# teaspoon.net
KiCad netlist of a schematic drawn in EAGLE
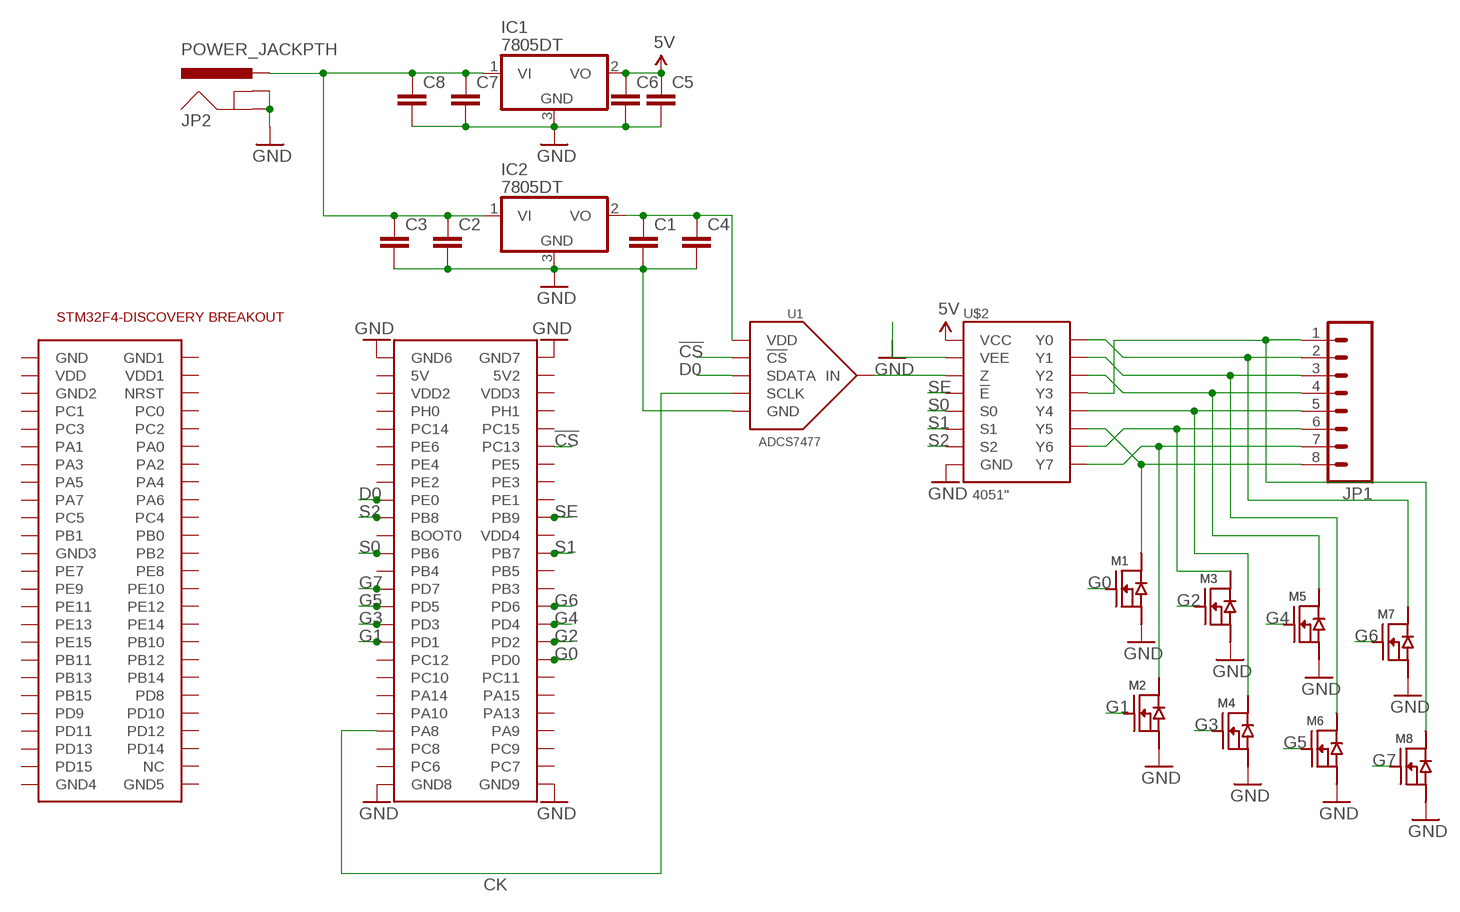
[diagram p0: schematic, sheet 1]

(export (version "E")
  (design (tool "Eeschema 10.0.6"))
  (components
    (comp (ref "C1")
      (value "C-EUC0805")
      (footprint "eagle-import:C0805")
      (libsource (lib "eagle-import") (part "C-EUC0805"))
    )
    (comp (ref "C2")
      (value "C-EUC0805")
      (footprint "eagle-import:C0805")
      (libsource (lib "eagle-import") (part "C-EUC0805"))
    )
    (comp (ref "C3")
      (value "C-EUC0805")
      (footprint "eagle-import:C0805")
      (libsource (lib "eagle-import") (part "C-EUC0805"))
    )
    (comp (ref "C4")
      (value "C-EUC0805")
      (footprint "eagle-import:C0805")
      (libsource (lib "eagle-import") (part "C-EUC0805"))
    )
    (comp (ref "C5")
      (value "C-EUC0805")
      (footprint "eagle-import:C0805")
      (libsource (lib "eagle-import") (part "C-EUC0805"))
    )
    (comp (ref "C6")
      (value "C-EUC0805")
      (footprint "eagle-import:C0805")
      (libsource (lib "eagle-import") (part "C-EUC0805"))
    )
    (comp (ref "C7")
      (value "C-EUC0805")
      (footprint "eagle-import:C0805")
      (libsource (lib "eagle-import") (part "C-EUC0805"))
    )
    (comp (ref "C8")
      (value "C-EUC0805")
      (footprint "eagle-import:C0805")
      (libsource (lib "eagle-import") (part "C-EUC0805"))
    )
    (comp (ref "IC1")
      (value "7805DT")
      (footprint "eagle-import:TO252")
      (libsource (lib "eagle-import") (part "78DT05"))
    )
    (comp (ref "IC2")
      (value "7805DT")
      (footprint "eagle-import:TO252")
      (libsource (lib "eagle-import") (part "78DT05"))
    )
    (comp (ref "JP1")
      (value "M08LONGPADS")
      (footprint "eagle-import:1X08_LONGPADS")
      (libsource (lib "eagle-import") (part "M08LONGPADS"))
    )
    (comp (ref "JP2")
      (value "POWER_JACKPTH")
      (footprint "eagle-import:POWER_JACK_PTH")
      (libsource (lib "eagle-import") (part "POWER_JACKPTH"))
    )
    (comp (ref "M1")
      (value "N-FET")
      (footprint "eagle-import:SOT23-3")
      (libsource (lib "eagle-import") (part "N-FET"))
    )
    (comp (ref "M2")
      (value "N-FET")
      (footprint "eagle-import:SOT23-3")
      (libsource (lib "eagle-import") (part "N-FET"))
    )
    (comp (ref "M3")
      (value "N-FET")
      (footprint "eagle-import:SOT23-3")
      (libsource (lib "eagle-import") (part "N-FET"))
    )
    (comp (ref "M4")
      (value "N-FET")
      (footprint "eagle-import:SOT23-3")
      (libsource (lib "eagle-import") (part "N-FET"))
    )
    (comp (ref "M5")
      (value "N-FET")
      (footprint "eagle-import:SOT23-3")
      (libsource (lib "eagle-import") (part "N-FET"))
    )
    (comp (ref "M6")
      (value "N-FET")
      (footprint "eagle-import:SOT23-3")
      (libsource (lib "eagle-import") (part "N-FET"))
    )
    (comp (ref "M7")
      (value "N-FET")
      (footprint "eagle-import:SOT23-3")
      (libsource (lib "eagle-import") (part "N-FET"))
    )
    (comp (ref "M8")
      (value "N-FET")
      (footprint "eagle-import:SOT23-3")
      (libsource (lib "eagle-import") (part "N-FET"))
    )
    (comp (ref "U$1")
      (value "STM32F4-DISCOVERY")
      (footprint "eagle-import:STM32F4-DISCOVERY")
      (libsource (lib "eagle-import") (part "STM32F4-DISCOVERY"))
    )
    (comp (ref "U$2")
      (value "4051\"")
      (footprint "eagle-import:TSSOP-16")
      (libsource (lib "eagle-import") (part "4051{dblquote}"))
    )
    (comp (ref "U1")
      (value "ADCS7477")
      (footprint "eagle-import:SOT-23-6")
      (libsource (lib "eagle-import") (part "ADCS7477"))
    )
  )
  (nets
    (net (code "1") (name "/CK") (class "Default")
      (node (ref "U$1") (pin "P$93") (pinfunction "PA8_P$93") (pintype "bidirectional"))
      (node (ref "U1") (pin "P$4") (pinfunction "SCLK_P$4") (pintype "bidirectional"))
    )
    (net (code "2") (name "/D0") (class "Default")
      (node (ref "U$1") (pin "P$67") (pinfunction "PE0_P$67") (pintype "bidirectional"))
      (node (ref "U1") (pin "P$5") (pinfunction "SDATA_P$5") (pintype "bidirectional"))
    )
    (net (code "3") (name "/G0") (class "Default")
      (node (ref "M1") (pin "1") (pinfunction "G_1") (pintype "bidirectional"))
      (node (ref "U$1") (pin "P$86") (pinfunction "PD0_P$86") (pintype "bidirectional"))
    )
    (net (code "4") (name "/G1") (class "Default")
      (node (ref "M2") (pin "1") (pinfunction "G_1") (pintype "bidirectional"))
      (node (ref "U$1") (pin "P$83") (pinfunction "PD1_P$83") (pintype "bidirectional"))
    )
    (net (code "5") (name "/G2") (class "Default")
      (node (ref "M3") (pin "1") (pinfunction "G_1") (pintype "bidirectional"))
      (node (ref "U$1") (pin "P$84") (pinfunction "PD2_P$84") (pintype "bidirectional"))
    )
    (net (code "6") (name "/G3") (class "Default")
      (node (ref "M4") (pin "1") (pinfunction "G_1") (pintype "bidirectional"))
      (node (ref "U$1") (pin "P$81") (pinfunction "PD3_P$81") (pintype "bidirectional"))
    )
    (net (code "7") (name "/G4") (class "Default")
      (node (ref "M5") (pin "1") (pinfunction "G_1") (pintype "bidirectional"))
      (node (ref "U$1") (pin "P$82") (pinfunction "PD4_P$82") (pintype "bidirectional"))
    )
    (net (code "8") (name "/G5") (class "Default")
      (node (ref "M6") (pin "1") (pinfunction "G_1") (pintype "bidirectional"))
      (node (ref "U$1") (pin "P$79") (pinfunction "PD5_P$79") (pintype "bidirectional"))
    )
    (net (code "9") (name "/G6") (class "Default")
      (node (ref "M7") (pin "1") (pinfunction "G_1") (pintype "bidirectional"))
      (node (ref "U$1") (pin "P$80") (pinfunction "PD6_P$80") (pintype "bidirectional"))
    )
    (net (code "10") (name "/G7") (class "Default")
      (node (ref "M8") (pin "1") (pinfunction "G_1") (pintype "bidirectional"))
      (node (ref "U$1") (pin "P$77") (pinfunction "PD7_P$77") (pintype "bidirectional"))
    )
    (net (code "11") (name "/S0") (class "Default")
      (node (ref "U$1") (pin "P$73") (pinfunction "PB6_P$73") (pintype "bidirectional"))
      (node (ref "U$2") (pin "P$11") (pinfunction "S0_P$11") (pintype "bidirectional"))
    )
    (net (code "12") (name "/S1") (class "Default")
      (node (ref "U$1") (pin "P$74") (pinfunction "PB7_P$74") (pintype "bidirectional"))
      (node (ref "U$2") (pin "P$10") (pinfunction "S1_P$10") (pintype "bidirectional"))
    )
    (net (code "13") (name "/S2") (class "Default")
      (node (ref "U$1") (pin "P$69") (pinfunction "PB8_P$69") (pintype "bidirectional"))
      (node (ref "U$2") (pin "P$9") (pinfunction "S2_P$9") (pintype "bidirectional"))
    )
    (net (code "14") (name "/SE") (class "Default")
      (node (ref "U$1") (pin "P$70") (pinfunction "PB9_P$70") (pintype "bidirectional"))
      (node (ref "U$2") (pin "P$6") (pinfunction "~{E}_P$6") (pintype "bidirectional"))
    )
    (net (code "15") (name "/~{CS}") (class "Default")
      (node (ref "U$1") (pin "P$62") (pinfunction "PC13_P$62") (pintype "bidirectional"))
      (node (ref "U1") (pin "P$6") (pinfunction "~{CS}_P$6") (pintype "bidirectional"))
    )
    (net (code "16") (name "5V") (class "Default")
      (node (ref "C5") (pin "1") (pinfunction "1_1") (pintype "passive"))
      (node (ref "C6") (pin "1") (pinfunction "1_1") (pintype "passive"))
      (node (ref "IC1") (pin "2") (pinfunction "VO_2") (pintype "passive"))
      (node (ref "U$2") (pin "P$16") (pinfunction "VCC_P$16") (pintype "bidirectional"))
    )
    (net (code "17") (name "GND") (class "Default")
      (node (ref "C1") (pin "2") (pinfunction "2_2") (pintype "passive"))
      (node (ref "C2") (pin "2") (pinfunction "2_2") (pintype "passive"))
      (node (ref "C3") (pin "2") (pinfunction "2_2") (pintype "passive"))
      (node (ref "C4") (pin "2") (pinfunction "2_2") (pintype "passive"))
      (node (ref "C5") (pin "2") (pinfunction "2_2") (pintype "passive"))
      (node (ref "C6") (pin "2") (pinfunction "2_2") (pintype "passive"))
      (node (ref "C7") (pin "2") (pinfunction "2_2") (pintype "passive"))
      (node (ref "C8") (pin "2") (pinfunction "2_2") (pintype "passive"))
      (node (ref "IC1") (pin "3") (pinfunction "GND_3") (pintype "passive"))
      (node (ref "IC2") (pin "3") (pinfunction "GND_3") (pintype "passive"))
      (node (ref "JP2") (pin "GND") (pinfunction "GND_GND") (pintype "bidirectional"))
      (node (ref "JP2") (pin "GNDBREAK") (pinfunction "GNDBREAK_GNDBREAK") (pintype "bidirectional"))
      (node (ref "M1") (pin "2") (pinfunction "S_2") (pintype "bidirectional"))
      (node (ref "M2") (pin "2") (pinfunction "S_2") (pintype "bidirectional"))
      (node (ref "M3") (pin "2") (pinfunction "S_2") (pintype "bidirectional"))
      (node (ref "M4") (pin "2") (pinfunction "S_2") (pintype "bidirectional"))
      (node (ref "M5") (pin "2") (pinfunction "S_2") (pintype "bidirectional"))
      (node (ref "M6") (pin "2") (pinfunction "S_2") (pintype "bidirectional"))
      (node (ref "M7") (pin "2") (pinfunction "S_2") (pintype "bidirectional"))
      (node (ref "M8") (pin "2") (pinfunction "S_2") (pintype "bidirectional"))
      (node (ref "U$1") (pin "P$100") (pinfunction "GND9_P$100") (pintype "bidirectional"))
      (node (ref "U$1") (pin "P$51") (pinfunction "GND6_P$51") (pintype "bidirectional"))
      (node (ref "U$1") (pin "P$52") (pinfunction "GND7_P$52") (pintype "bidirectional"))
      (node (ref "U$1") (pin "P$99") (pinfunction "GND8_P$99") (pintype "bidirectional"))
      (node (ref "U$2") (pin "P$7") (pinfunction "VEE_P$7") (pintype "bidirectional"))
      (node (ref "U$2") (pin "P$8") (pinfunction "GND_P$8") (pintype "bidirectional"))
      (node (ref "U1") (pin "P$2") (pinfunction "GND_P$2") (pintype "bidirectional"))
    )
    (net (code "18") (name "Net-(IC1-VI)") (class "Default")
      (node (ref "C2") (pin "1") (pinfunction "1_1") (pintype "passive"))
      (node (ref "C3") (pin "1") (pinfunction "1_1") (pintype "passive"))
      (node (ref "C7") (pin "1") (pinfunction "1_1") (pintype "passive"))
      (node (ref "C8") (pin "1") (pinfunction "1_1") (pintype "passive"))
      (node (ref "IC1") (pin "1") (pinfunction "VI_1") (pintype "input"))
      (node (ref "IC2") (pin "1") (pinfunction "VI_1") (pintype "input"))
      (node (ref "JP2") (pin "PWR") (pinfunction "PWR_PWR") (pintype "bidirectional"))
    )
    (net (code "19") (name "Net-(IC2-VO)") (class "Default")
      (node (ref "C1") (pin "1") (pinfunction "1_1") (pintype "passive"))
      (node (ref "C4") (pin "1") (pinfunction "1_1") (pintype "passive"))
      (node (ref "IC2") (pin "2") (pinfunction "VO_2") (pintype "passive"))
      (node (ref "U1") (pin "P$1") (pinfunction "VDD_P$1") (pintype "bidirectional"))
    )
    (net (code "20") (name "Net-(M1-D)") (class "Default")
      (node (ref "JP1") (pin "8") (pinfunction "8_8") (pintype "passive"))
      (node (ref "M1") (pin "3") (pinfunction "D_3") (pintype "bidirectional"))
      (node (ref "U$2") (pin "P$5") (pinfunction "Y5_P$5") (pintype "bidirectional"))
    )
    (net (code "21") (name "Net-(M2-D)") (class "Default")
      (node (ref "JP1") (pin "7") (pinfunction "7_7") (pintype "passive"))
      (node (ref "M2") (pin "3") (pinfunction "D_3") (pintype "bidirectional"))
      (node (ref "U$2") (pin "P$4") (pinfunction "Y7_P$4") (pintype "bidirectional"))
    )
    (net (code "22") (name "Net-(M3-D)") (class "Default")
      (node (ref "JP1") (pin "6") (pinfunction "6_6") (pintype "passive"))
      (node (ref "M3") (pin "3") (pinfunction "D_3") (pintype "bidirectional"))
      (node (ref "U$2") (pin "P$2") (pinfunction "Y6_P$2") (pintype "bidirectional"))
    )
    (net (code "23") (name "Net-(M4-D)") (class "Default")
      (node (ref "JP1") (pin "5") (pinfunction "5_5") (pintype "passive"))
      (node (ref "M4") (pin "3") (pinfunction "D_3") (pintype "bidirectional"))
      (node (ref "U$2") (pin "P$1") (pinfunction "Y4_P$1") (pintype "bidirectional"))
    )
    (net (code "24") (name "Net-(M5-D)") (class "Default")
      (node (ref "JP1") (pin "4") (pinfunction "4_4") (pintype "passive"))
      (node (ref "M5") (pin "3") (pinfunction "D_3") (pintype "bidirectional"))
      (node (ref "U$2") (pin "P$15") (pinfunction "Y2_P$15") (pintype "bidirectional"))
    )
    (net (code "25") (name "Net-(M6-D)") (class "Default")
      (node (ref "JP1") (pin "3") (pinfunction "3_3") (pintype "passive"))
      (node (ref "M6") (pin "3") (pinfunction "D_3") (pintype "bidirectional"))
      (node (ref "U$2") (pin "P$14") (pinfunction "Y1_P$14") (pintype "bidirectional"))
    )
    (net (code "26") (name "Net-(M7-D)") (class "Default")
      (node (ref "JP1") (pin "2") (pinfunction "2_2") (pintype "passive"))
      (node (ref "M7") (pin "3") (pinfunction "D_3") (pintype "bidirectional"))
      (node (ref "U$2") (pin "P$13") (pinfunction "Y0_P$13") (pintype "bidirectional"))
    )
    (net (code "27") (name "Net-(M8-D)") (class "Default")
      (node (ref "JP1") (pin "1") (pinfunction "1_1") (pintype "passive"))
      (node (ref "M8") (pin "3") (pinfunction "D_3") (pintype "bidirectional"))
      (node (ref "U$2") (pin "P$12") (pinfunction "Y3_P$12") (pintype "bidirectional"))
    )
    (net (code "28") (name "Net-(U$2-Z)") (class "Default")
      (node (ref "U$2") (pin "P$3") (pinfunction "Z_P$3") (pintype "bidirectional"))
      (node (ref "U1") (pin "P$3") (pinfunction "IN_P$3") (pintype "bidirectional"))
    )
    (net (code "29") (name "unconnected-(U$1-5V-PadP$53)") (class "Default")
      (node (ref "U$1") (pin "P$53") (pinfunction "5V_P$53") (pintype "bidirectional"))
    )
    (net (code "30") (name "unconnected-(U$1-5V2-PadP$54)") (class "Default")
      (node (ref "U$1") (pin "P$54") (pinfunction "5V2_P$54") (pintype "bidirectional"))
    )
    (net (code "31") (name "unconnected-(U$1-BOOT0-PadP$71)") (class "Default")
      (node (ref "U$1") (pin "P$71") (pinfunction "BOOT0_P$71") (pintype "bidirectional"))
    )
    (net (code "32") (name "unconnected-(U$1-GND-PadP$1)") (class "Default")
      (node (ref "U$1") (pin "P$1") (pinfunction "GND_P$1") (pintype "bidirectional"))
    )
    (net (code "33") (name "unconnected-(U$1-GND1-PadP$2)") (class "Default")
      (node (ref "U$1") (pin "P$2") (pinfunction "GND1_P$2") (pintype "bidirectional"))
    )
    (net (code "34") (name "unconnected-(U$1-GND2-PadP$5)") (class "Default")
      (node (ref "U$1") (pin "P$5") (pinfunction "GND2_P$5") (pintype "bidirectional"))
    )
    (net (code "35") (name "unconnected-(U$1-GND3-PadP$23)") (class "Default")
      (node (ref "U$1") (pin "P$23") (pinfunction "GND3_P$23") (pintype "bidirectional"))
    )
    (net (code "36") (name "unconnected-(U$1-GND4-PadP$49)") (class "Default")
      (node (ref "U$1") (pin "P$49") (pinfunction "GND4_P$49") (pintype "bidirectional"))
    )
    (net (code "37") (name "unconnected-(U$1-GND5-PadP$50)") (class "Default")
      (node (ref "U$1") (pin "P$50") (pinfunction "GND5_P$50") (pintype "bidirectional"))
    )
    (net (code "38") (name "unconnected-(U$1-NC-PadP$48)") (class "Default")
      (node (ref "U$1") (pin "P$48") (pinfunction "NC_P$48") (pintype "bidirectional"))
    )
    (net (code "39") (name "unconnected-(U$1-NRST-PadP$6)") (class "Default")
      (node (ref "U$1") (pin "P$6") (pinfunction "NRST_P$6") (pintype "bidirectional"))
    )
    (net (code "40") (name "unconnected-(U$1-PA0-PadP$12)") (class "Default")
      (node (ref "U$1") (pin "P$12") (pinfunction "PA0_P$12") (pintype "bidirectional"))
    )
    (net (code "41") (name "unconnected-(U$1-PA1-PadP$11)") (class "Default")
      (node (ref "U$1") (pin "P$11") (pinfunction "PA1_P$11") (pintype "bidirectional"))
    )
    (net (code "42") (name "unconnected-(U$1-PA2-PadP$14)") (class "Default")
      (node (ref "U$1") (pin "P$14") (pinfunction "PA2_P$14") (pintype "bidirectional"))
    )
    (net (code "43") (name "unconnected-(U$1-PA3-PadP$13)") (class "Default")
      (node (ref "U$1") (pin "P$13") (pinfunction "PA3_P$13") (pintype "bidirectional"))
    )
    (net (code "44") (name "unconnected-(U$1-PA4-PadP$16)") (class "Default")
      (node (ref "U$1") (pin "P$16") (pinfunction "PA4_P$16") (pintype "bidirectional"))
    )
    (net (code "45") (name "unconnected-(U$1-PA5-PadP$15)") (class "Default")
      (node (ref "U$1") (pin "P$15") (pinfunction "PA5_P$15") (pintype "bidirectional"))
    )
    (net (code "46") (name "unconnected-(U$1-PA6-PadP$18)") (class "Default")
      (node (ref "U$1") (pin "P$18") (pinfunction "PA6_P$18") (pintype "bidirectional"))
    )
    (net (code "47") (name "unconnected-(U$1-PA7-PadP$17)") (class "Default")
      (node (ref "U$1") (pin "P$17") (pinfunction "PA7_P$17") (pintype "bidirectional"))
    )
    (net (code "48") (name "unconnected-(U$1-PA9-PadP$94)") (class "Default")
      (node (ref "U$1") (pin "P$94") (pinfunction "PA9_P$94") (pintype "bidirectional"))
    )
    (net (code "49") (name "unconnected-(U$1-PA10-PadP$91)") (class "Default")
      (node (ref "U$1") (pin "P$91") (pinfunction "PA10_P$91") (pintype "bidirectional"))
    )
    (net (code "50") (name "unconnected-(U$1-PA13-PadP$92)") (class "Default")
      (node (ref "U$1") (pin "P$92") (pinfunction "PA13_P$92") (pintype "bidirectional"))
    )
    (net (code "51") (name "unconnected-(U$1-PA14-PadP$89)") (class "Default")
      (node (ref "U$1") (pin "P$89") (pinfunction "PA14_P$89") (pintype "bidirectional"))
    )
    (net (code "52") (name "unconnected-(U$1-PA15-PadP$90)") (class "Default")
      (node (ref "U$1") (pin "P$90") (pinfunction "PA15_P$90") (pintype "bidirectional"))
    )
    (net (code "53") (name "unconnected-(U$1-PB0-PadP$22)") (class "Default")
      (node (ref "U$1") (pin "P$22") (pinfunction "PB0_P$22") (pintype "bidirectional"))
    )
    (net (code "54") (name "unconnected-(U$1-PB1-PadP$21)") (class "Default")
      (node (ref "U$1") (pin "P$21") (pinfunction "PB1_P$21") (pintype "bidirectional"))
    )
    (net (code "55") (name "unconnected-(U$1-PB2-PadP$24)") (class "Default")
      (node (ref "U$1") (pin "P$24") (pinfunction "PB2_P$24") (pintype "bidirectional"))
    )
    (net (code "56") (name "unconnected-(U$1-PB3-PadP$78)") (class "Default")
      (node (ref "U$1") (pin "P$78") (pinfunction "PB3_P$78") (pintype "bidirectional"))
    )
    (net (code "57") (name "unconnected-(U$1-PB4-PadP$75)") (class "Default")
      (node (ref "U$1") (pin "P$75") (pinfunction "PB4_P$75") (pintype "bidirectional"))
    )
    (net (code "58") (name "unconnected-(U$1-PB5-PadP$76)") (class "Default")
      (node (ref "U$1") (pin "P$76") (pinfunction "PB5_P$76") (pintype "bidirectional"))
    )
    (net (code "59") (name "unconnected-(U$1-PB10-PadP$34)") (class "Default")
      (node (ref "U$1") (pin "P$34") (pinfunction "PB10_P$34") (pintype "bidirectional"))
    )
    (net (code "60") (name "unconnected-(U$1-PB11-PadP$35)") (class "Default")
      (node (ref "U$1") (pin "P$35") (pinfunction "PB11_P$35") (pintype "bidirectional"))
    )
    (net (code "61") (name "unconnected-(U$1-PB12-PadP$36)") (class "Default")
      (node (ref "U$1") (pin "P$36") (pinfunction "PB12_P$36") (pintype "bidirectional"))
    )
    (net (code "62") (name "unconnected-(U$1-PB13-PadP$37)") (class "Default")
      (node (ref "U$1") (pin "P$37") (pinfunction "PB13_P$37") (pintype "bidirectional"))
    )
    (net (code "63") (name "unconnected-(U$1-PB14-PadP$38)") (class "Default")
      (node (ref "U$1") (pin "P$38") (pinfunction "PB14_P$38") (pintype "bidirectional"))
    )
    (net (code "64") (name "unconnected-(U$1-PB15-PadP$39)") (class "Default")
      (node (ref "U$1") (pin "P$39") (pinfunction "PB15_P$39") (pintype "bidirectional"))
    )
    (net (code "65") (name "unconnected-(U$1-PC0-PadP$8)") (class "Default")
      (node (ref "U$1") (pin "P$8") (pinfunction "PC0_P$8") (pintype "bidirectional"))
    )
    (net (code "66") (name "unconnected-(U$1-PC1-PadP$7)") (class "Default")
      (node (ref "U$1") (pin "P$7") (pinfunction "PC1_P$7") (pintype "bidirectional"))
    )
    (net (code "67") (name "unconnected-(U$1-PC2-PadP$10)") (class "Default")
      (node (ref "U$1") (pin "P$10") (pinfunction "PC2_P$10") (pintype "bidirectional"))
    )
    (net (code "68") (name "unconnected-(U$1-PC3-PadP$9)") (class "Default")
      (node (ref "U$1") (pin "P$9") (pinfunction "PC3_P$9") (pintype "bidirectional"))
    )
    (net (code "69") (name "unconnected-(U$1-PC4-PadP$20)") (class "Default")
      (node (ref "U$1") (pin "P$20") (pinfunction "PC4_P$20") (pintype "bidirectional"))
    )
    (net (code "70") (name "unconnected-(U$1-PC5-PadP$19)") (class "Default")
      (node (ref "U$1") (pin "P$19") (pinfunction "PC5_P$19") (pintype "bidirectional"))
    )
    (net (code "71") (name "unconnected-(U$1-PC6-PadP$97)") (class "Default")
      (node (ref "U$1") (pin "P$97") (pinfunction "PC6_P$97") (pintype "bidirectional"))
    )
    (net (code "72") (name "unconnected-(U$1-PC7-PadP$98)") (class "Default")
      (node (ref "U$1") (pin "P$98") (pinfunction "PC7_P$98") (pintype "bidirectional"))
    )
    (net (code "73") (name "unconnected-(U$1-PC8-PadP$95)") (class "Default")
      (node (ref "U$1") (pin "P$95") (pinfunction "PC8_P$95") (pintype "bidirectional"))
    )
    (net (code "74") (name "unconnected-(U$1-PC9-PadP$96)") (class "Default")
      (node (ref "U$1") (pin "P$96") (pinfunction "PC9_P$96") (pintype "bidirectional"))
    )
    (net (code "75") (name "unconnected-(U$1-PC10-PadP$87)") (class "Default")
      (node (ref "U$1") (pin "P$87") (pinfunction "PC10_P$87") (pintype "bidirectional"))
    )
    (net (code "76") (name "unconnected-(U$1-PC11-PadP$88)") (class "Default")
      (node (ref "U$1") (pin "P$88") (pinfunction "PC11_P$88") (pintype "bidirectional"))
    )
    (net (code "77") (name "unconnected-(U$1-PC12-PadP$85)") (class "Default")
      (node (ref "U$1") (pin "P$85") (pinfunction "PC12_P$85") (pintype "bidirectional"))
    )
    (net (code "78") (name "unconnected-(U$1-PC14-PadP$59)") (class "Default")
      (node (ref "U$1") (pin "P$59") (pinfunction "PC14_P$59") (pintype "bidirectional"))
    )
    (net (code "79") (name "unconnected-(U$1-PC15-PadP$60)") (class "Default")
      (node (ref "U$1") (pin "P$60") (pinfunction "PC15_P$60") (pintype "bidirectional"))
    )
    (net (code "80") (name "unconnected-(U$1-PD8-PadP$40)") (class "Default")
      (node (ref "U$1") (pin "P$40") (pinfunction "PD8_P$40") (pintype "bidirectional"))
    )
    (net (code "81") (name "unconnected-(U$1-PD9-PadP$41)") (class "Default")
      (node (ref "U$1") (pin "P$41") (pinfunction "PD9_P$41") (pintype "bidirectional"))
    )
    (net (code "82") (name "unconnected-(U$1-PD10-PadP$42)") (class "Default")
      (node (ref "U$1") (pin "P$42") (pinfunction "PD10_P$42") (pintype "bidirectional"))
    )
    (net (code "83") (name "unconnected-(U$1-PD11-PadP$43)") (class "Default")
      (node (ref "U$1") (pin "P$43") (pinfunction "PD11_P$43") (pintype "bidirectional"))
    )
    (net (code "84") (name "unconnected-(U$1-PD12-PadP$44)") (class "Default")
      (node (ref "U$1") (pin "P$44") (pinfunction "PD12_P$44") (pintype "bidirectional"))
    )
    (net (code "85") (name "unconnected-(U$1-PD13-PadP$45)") (class "Default")
      (node (ref "U$1") (pin "P$45") (pinfunction "PD13_P$45") (pintype "bidirectional"))
    )
    (net (code "86") (name "unconnected-(U$1-PD14-PadP$46)") (class "Default")
      (node (ref "U$1") (pin "P$46") (pinfunction "PD14_P$46") (pintype "bidirectional"))
    )
    (net (code "87") (name "unconnected-(U$1-PD15-PadP$47)") (class "Default")
      (node (ref "U$1") (pin "P$47") (pinfunction "PD15_P$47") (pintype "bidirectional"))
    )
    (net (code "88") (name "unconnected-(U$1-PE1-PadP$68)") (class "Default")
      (node (ref "U$1") (pin "P$68") (pinfunction "PE1_P$68") (pintype "bidirectional"))
    )
    (net (code "89") (name "unconnected-(U$1-PE2-PadP$65)") (class "Default")
      (node (ref "U$1") (pin "P$65") (pinfunction "PE2_P$65") (pintype "bidirectional"))
    )
    (net (code "90") (name "unconnected-(U$1-PE3-PadP$66)") (class "Default")
      (node (ref "U$1") (pin "P$66") (pinfunction "PE3_P$66") (pintype "bidirectional"))
    )
    (net (code "91") (name "unconnected-(U$1-PE4-PadP$63)") (class "Default")
      (node (ref "U$1") (pin "P$63") (pinfunction "PE4_P$63") (pintype "bidirectional"))
    )
    (net (code "92") (name "unconnected-(U$1-PE5-PadP$64)") (class "Default")
      (node (ref "U$1") (pin "P$64") (pinfunction "PE5_P$64") (pintype "bidirectional"))
    )
    (net (code "93") (name "unconnected-(U$1-PE6-PadP$61)") (class "Default")
      (node (ref "U$1") (pin "P$61") (pinfunction "PE6_P$61") (pintype "bidirectional"))
    )
    (net (code "94") (name "unconnected-(U$1-PE7-PadP$25)") (class "Default")
      (node (ref "U$1") (pin "P$25") (pinfunction "PE7_P$25") (pintype "bidirectional"))
    )
    (net (code "95") (name "unconnected-(U$1-PE8-PadP$26)") (class "Default")
      (node (ref "U$1") (pin "P$26") (pinfunction "PE8_P$26") (pintype "bidirectional"))
    )
    (net (code "96") (name "unconnected-(U$1-PE9-PadP$27)") (class "Default")
      (node (ref "U$1") (pin "P$27") (pinfunction "PE9_P$27") (pintype "bidirectional"))
    )
    (net (code "97") (name "unconnected-(U$1-PE10-PadP$28)") (class "Default")
      (node (ref "U$1") (pin "P$28") (pinfunction "PE10_P$28") (pintype "bidirectional"))
    )
    (net (code "98") (name "unconnected-(U$1-PE11-PadP$29)") (class "Default")
      (node (ref "U$1") (pin "P$29") (pinfunction "PE11_P$29") (pintype "bidirectional"))
    )
    (net (code "99") (name "unconnected-(U$1-PE12-PadP$30)") (class "Default")
      (node (ref "U$1") (pin "P$30") (pinfunction "PE12_P$30") (pintype "bidirectional"))
    )
    (net (code "100") (name "unconnected-(U$1-PE13-PadP$31)") (class "Default")
      (node (ref "U$1") (pin "P$31") (pinfunction "PE13_P$31") (pintype "bidirectional"))
    )
    (net (code "101") (name "unconnected-(U$1-PE14-PadP$32)") (class "Default")
      (node (ref "U$1") (pin "P$32") (pinfunction "PE14_P$32") (pintype "bidirectional"))
    )
    (net (code "102") (name "unconnected-(U$1-PE15-PadP$33)") (class "Default")
      (node (ref "U$1") (pin "P$33") (pinfunction "PE15_P$33") (pintype "bidirectional"))
    )
    (net (code "103") (name "unconnected-(U$1-PH0-PadP$57)") (class "Default")
      (node (ref "U$1") (pin "P$57") (pinfunction "PH0_P$57") (pintype "bidirectional"))
    )
    (net (code "104") (name "unconnected-(U$1-PH1-PadP$58)") (class "Default")
      (node (ref "U$1") (pin "P$58") (pinfunction "PH1_P$58") (pintype "bidirectional"))
    )
    (net (code "105") (name "unconnected-(U$1-VDD-PadP$3)") (class "Default")
      (node (ref "U$1") (pin "P$3") (pinfunction "VDD_P$3") (pintype "bidirectional"))
    )
    (net (code "106") (name "unconnected-(U$1-VDD1-PadP$4)") (class "Default")
      (node (ref "U$1") (pin "P$4") (pinfunction "VDD1_P$4") (pintype "bidirectional"))
    )
    (net (code "107") (name "unconnected-(U$1-VDD2-PadP$55)") (class "Default")
      (node (ref "U$1") (pin "P$55") (pinfunction "VDD2_P$55") (pintype "bidirectional"))
    )
    (net (code "108") (name "unconnected-(U$1-VDD3-PadP$56)") (class "Default")
      (node (ref "U$1") (pin "P$56") (pinfunction "VDD3_P$56") (pintype "bidirectional"))
    )
    (net (code "109") (name "unconnected-(U$1-VDD4-PadP$72)") (class "Default")
      (node (ref "U$1") (pin "P$72") (pinfunction "VDD4_P$72") (pintype "bidirectional"))
    )
  )
)
